# rs232-rs485-transceiver.net
KiCad netlist of a schematic drawn in Altium Designer
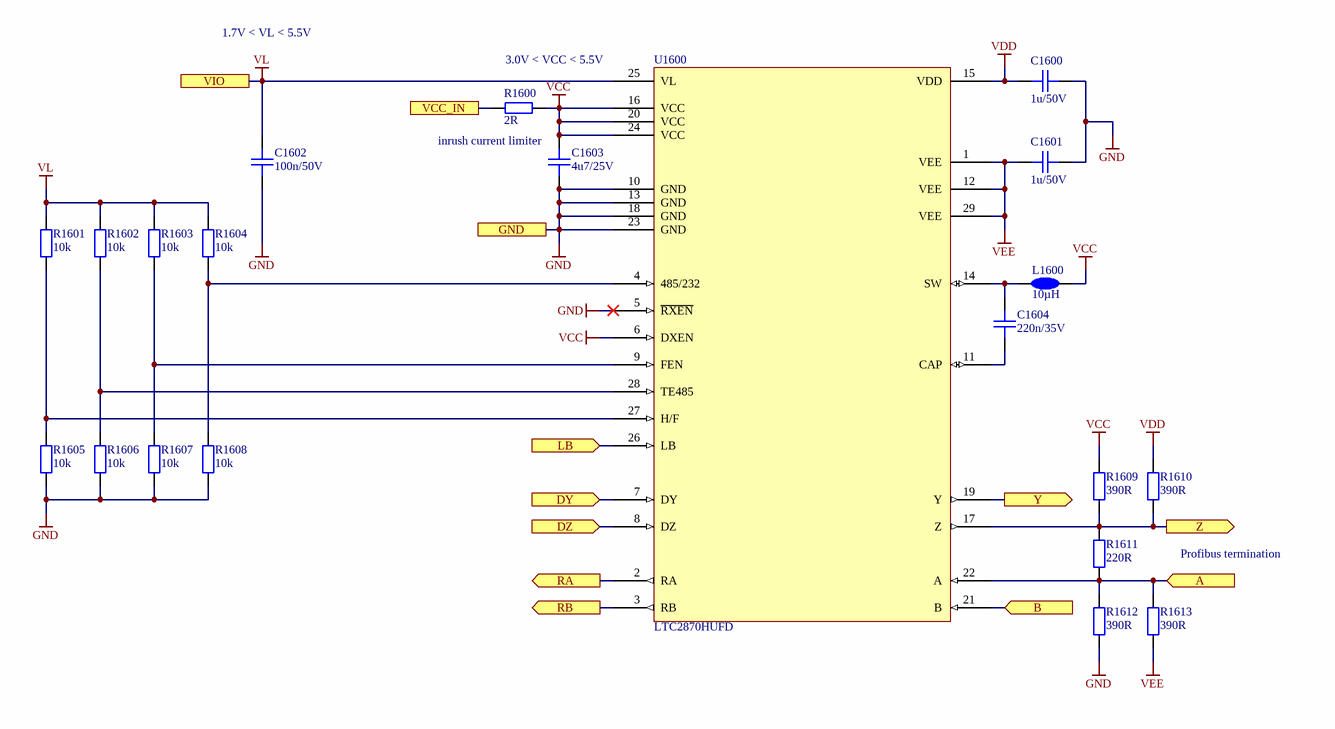
[diagram p0: rs232-rs485-transceiver.SchDoc]

(export (version "E")
  (design (tool "Eeschema 10.0.6"))
  (components
    (comp (ref "C1600")
      (value "1u/50V")
      (footprint "CAPC1608X08N")
      (description "MLCC")
      (fields (field (name "PART NUMBER") "gen_C_ceramic_1u_50V_X7R_0603") (field (name "TOLERANCE") "± 10%"))
      (libsource (lib "OE750") (part "C"))
    )
    (comp (ref "C1601")
      (value "1u/50V")
      (footprint "CAPC1608X08N")
      (description "MLCC")
      (fields (field (name "PART NUMBER") "gen_C_ceramic_1u_50V_X7R_0603") (field (name "TOLERANCE") "± 10%"))
      (libsource (lib "OE750") (part "C"))
    )
    (comp (ref "C1602")
      (value "100n/50V")
      (footprint "CAPC1005X06N")
      (description "MLCC")
      (fields (field (name "PART NUMBER") "gen_C_ceramic_100n_50V_X7R_0402"))
      (libsource (lib "OE750") (part "C"))
    )
    (comp (ref "C1603")
      (value "4u7/25V")
      (footprint "CAPC2012X14N")
      (description "MLCC")
      (fields (field (name "PART NUMBER") "gen_C_ceramic_4u7_25V_X7R_0805"))
      (libsource (lib "OE750") (part "C"))
    )
    (comp (ref "C1604")
      (value "220n/35V")
      (footprint "CAPC1005X06N")
      (description "MLCC")
      (fields (field (name "PART NUMBER") "gen_C_ceramic_220n_35V_X7R_0402"))
      (libsource (lib "OE750") (part "C"))
    )
    (comp (ref "L1600")
      (value "10µH")
      (footprint "INDC2012X14N")
      (description "Power Inductor")
      (fields (field (name "PART NUMBER") "LQM21DH100M70L") (field (name "MANUFACTURER") "Murata"))
      (libsource (lib "OE750") (part "L"))
    )
    (comp (ref "R1600")
      (value "2R")
      (footprint "RESC2012X05N")
      (description "SMD Resistor 2R 0805")
      (fields (field (name "PART NUMBER") "gen_R_2R_0805") (field (name "TOLERANCE") "1%"))
      (libsource (lib "OE750") (part "R"))
    )
    (comp (ref "R1601")
      (value "10k")
      (footprint "RESC1005X04N")
      (description "SMD Resistor 10k 0402")
      (fields (field (name "PART NUMBER") "gen_R_10k_0402") (field (name "TOLERANCE") "1%"))
      (libsource (lib "OE750") (part "R"))
    )
    (comp (ref "R1602")
      (value "10k")
      (footprint "RESC1005X04N")
      (description "SMD Resistor 10k 0402")
      (fields (field (name "PART NUMBER") "gen_R_10k_0402") (field (name "TOLERANCE") "1%"))
      (libsource (lib "OE750") (part "R"))
    )
    (comp (ref "R1603")
      (value "10k")
      (footprint "RESC1005X04N")
      (description "SMD Resistor 10k 0402")
      (fields (field (name "PART NUMBER") "gen_R_10k_0402") (field (name "TOLERANCE") "1%"))
      (libsource (lib "OE750") (part "R"))
    )
    (comp (ref "R1604")
      (value "10k")
      (footprint "RESC1005X04N")
      (description "SMD Resistor 10k 0402")
      (fields (field (name "PART NUMBER") "gen_R_10k_0402") (field (name "TOLERANCE") "1%"))
      (libsource (lib "OE750") (part "R"))
    )
    (comp (ref "R1605")
      (value "10k")
      (footprint "RESC1005X04N")
      (description "SMD Resistor 10k 0402")
      (fields (field (name "PART NUMBER") "gen_R_10k_0402") (field (name "TOLERANCE") "1%"))
      (libsource (lib "OE750") (part "R"))
    )
    (comp (ref "R1606")
      (value "10k")
      (footprint "RESC1005X04N")
      (description "SMD Resistor 10k 0402")
      (fields (field (name "PART NUMBER") "gen_R_10k_0402") (field (name "TOLERANCE") "1%"))
      (libsource (lib "OE750") (part "R"))
    )
    (comp (ref "R1607")
      (value "10k")
      (footprint "RESC1005X04N")
      (description "SMD Resistor 10k 0402")
      (fields (field (name "PART NUMBER") "gen_R_10k_0402") (field (name "TOLERANCE") "1%"))
      (libsource (lib "OE750") (part "R"))
    )
    (comp (ref "R1608")
      (value "10k")
      (footprint "RESC1005X04N")
      (description "SMD Resistor 10k 0402")
      (fields (field (name "PART NUMBER") "gen_R_10k_0402") (field (name "TOLERANCE") "1%"))
      (libsource (lib "OE750") (part "R"))
    )
    (comp (ref "R1609")
      (value "390R")
      (footprint "RESC1005X04N")
      (description "SMD Resistor 390R 0402")
      (fields (field (name "PART NUMBER") "gen_R_390R_0402") (field (name "TOLERANCE") "1%"))
      (libsource (lib "OE750") (part "R"))
    )
    (comp (ref "R1610")
      (value "390R")
      (footprint "RESC1005X04N")
      (description "SMD Resistor 390R 0402")
      (fields (field (name "PART NUMBER") "gen_R_390R_0402") (field (name "TOLERANCE") "1%"))
      (libsource (lib "OE750") (part "R"))
    )
    (comp (ref "R1611")
      (value "220R")
      (footprint "RESC1005X04N")
      (description "SMD Resistor 220R 0402")
      (fields (field (name "PART NUMBER") "gen_R_220R_0402") (field (name "TOLERANCE") "1%"))
      (libsource (lib "OE750") (part "R"))
    )
    (comp (ref "R1612")
      (value "390R")
      (footprint "RESC1005X04N")
      (description "SMD Resistor 390R 0402")
      (fields (field (name "PART NUMBER") "gen_R_390R_0402") (field (name "TOLERANCE") "1%"))
      (libsource (lib "OE750") (part "R"))
    )
    (comp (ref "R1613")
      (value "390R")
      (footprint "RESC1005X04N")
      (description "SMD Resistor 390R 0402")
      (fields (field (name "PART NUMBER") "gen_R_390R_0402") (field (name "TOLERANCE") "1%"))
      (libsource (lib "OE750") (part "R"))
    )
    (comp (ref "U1600")
      (value "LTC2870HUFD")
      (footprint "LTC2870-UFD")
      (description "RS-232-IC-Interface RS232/RS485 Multiprotocol Transceiver with Integrated Termination")
      (fields (field (name "MANUFACTURER") "Analog Devices"))
      (libsource (lib "OE750") (part "LTC2870"))
    )
  )
  (nets
    (net (code "1") (name "/A") (class "Default")
      (node (ref "R1611") (pin "1") (pinfunction "1_1") (pintype "passive"))
      (node (ref "R1612") (pin "2") (pinfunction "2_2") (pintype "passive"))
      (node (ref "R1613") (pin "2") (pinfunction "2_2") (pintype "passive"))
      (node (ref "U1600") (pin "22") (pinfunction "A_22") (pintype "input"))
    )
    (net (code "2") (name "/B") (class "Default")
      (node (ref "U1600") (pin "21") (pinfunction "B_21") (pintype "input"))
    )
    (net (code "3") (name "/DY") (class "Default")
      (node (ref "U1600") (pin "7") (pinfunction "DY_7") (pintype "input"))
    )
    (net (code "4") (name "/DZ") (class "Default")
      (node (ref "U1600") (pin "8") (pinfunction "DZ_8") (pintype "input"))
    )
    (net (code "5") (name "/LB") (class "Default")
      (node (ref "U1600") (pin "26") (pinfunction "LB_26") (pintype "input"))
    )
    (net (code "6") (name "/RA") (class "Default")
      (node (ref "U1600") (pin "2") (pinfunction "RA_2") (pintype "output"))
    )
    (net (code "7") (name "/RB") (class "Default")
      (node (ref "U1600") (pin "3") (pinfunction "RB_3") (pintype "output"))
    )
    (net (code "8") (name "/VCC_IN") (class "Default")
      (node (ref "R1600") (pin "1") (pinfunction "1_1") (pintype "passive"))
    )
    (net (code "9") (name "/Y") (class "Default")
      (node (ref "U1600") (pin "19") (pinfunction "Y_19") (pintype "output"))
    )
    (net (code "10") (name "/Z") (class "Default")
      (node (ref "R1609") (pin "1") (pinfunction "1_1") (pintype "passive"))
      (node (ref "R1610") (pin "1") (pinfunction "1_1") (pintype "passive"))
      (node (ref "R1611") (pin "2") (pinfunction "2_2") (pintype "passive"))
      (node (ref "U1600") (pin "17") (pinfunction "Z_17") (pintype "output"))
    )
    (net (code "11") (name "GND") (class "Default")
      (node (ref "C1600") (pin "2") (pinfunction "2_2") (pintype "passive"))
      (node (ref "C1601") (pin "2") (pinfunction "2_2") (pintype "passive"))
      (node (ref "C1602") (pin "1") (pinfunction "1_1") (pintype "passive"))
      (node (ref "C1603") (pin "1") (pinfunction "1_1") (pintype "passive"))
      (node (ref "R1605") (pin "1") (pinfunction "1_1") (pintype "passive"))
      (node (ref "R1606") (pin "1") (pinfunction "1_1") (pintype "passive"))
      (node (ref "R1607") (pin "1") (pinfunction "1_1") (pintype "passive"))
      (node (ref "R1608") (pin "1") (pinfunction "1_1") (pintype "passive"))
      (node (ref "R1612") (pin "1") (pinfunction "1_1") (pintype "passive"))
      (node (ref "U1600") (pin "10") (pinfunction "GND_10") (pintype "power_in"))
      (node (ref "U1600") (pin "13") (pinfunction "GND_13") (pintype "power_in"))
      (node (ref "U1600") (pin "18") (pinfunction "GND_18") (pintype "power_in"))
      (node (ref "U1600") (pin "23") (pinfunction "GND_23") (pintype "power_in"))
      (node (ref "U1600") (pin "5") (pinfunction "RXEN_5") (pintype "input"))
    )
    (net (code "12") (name "Net-(U1600-485{slash}232)") (class "Default")
      (node (ref "R1604") (pin "1") (pinfunction "1_1") (pintype "passive"))
      (node (ref "R1608") (pin "2") (pinfunction "2_2") (pintype "passive"))
      (node (ref "U1600") (pin "4") (pinfunction "485/232_4") (pintype "input"))
    )
    (net (code "13") (name "Net-(U1600-CAP)") (class "Default")
      (node (ref "C1604") (pin "1") (pinfunction "1_1") (pintype "passive"))
      (node (ref "U1600") (pin "11") (pinfunction "CAP_11") (pintype "bidirectional"))
    )
    (net (code "14") (name "Net-(U1600-FEN)") (class "Default")
      (node (ref "R1603") (pin "1") (pinfunction "1_1") (pintype "passive"))
      (node (ref "R1607") (pin "2") (pinfunction "2_2") (pintype "passive"))
      (node (ref "U1600") (pin "9") (pinfunction "FEN_9") (pintype "input"))
    )
    (net (code "15") (name "Net-(U1600-H{slash}F)") (class "Default")
      (node (ref "R1601") (pin "1") (pinfunction "1_1") (pintype "passive"))
      (node (ref "R1605") (pin "2") (pinfunction "2_2") (pintype "passive"))
      (node (ref "U1600") (pin "27") (pinfunction "H/F_27") (pintype "input"))
    )
    (net (code "16") (name "Net-(U1600-SW)") (class "Default")
      (node (ref "C1604") (pin "2") (pinfunction "2_2") (pintype "passive"))
      (node (ref "L1600") (pin "1") (pinfunction "1_1") (pintype "passive"))
      (node (ref "U1600") (pin "14") (pinfunction "SW_14") (pintype "bidirectional"))
    )
    (net (code "17") (name "Net-(U1600-TE485)") (class "Default")
      (node (ref "R1602") (pin "1") (pinfunction "1_1") (pintype "passive"))
      (node (ref "R1606") (pin "2") (pinfunction "2_2") (pintype "passive"))
      (node (ref "U1600") (pin "28") (pinfunction "TE485_28") (pintype "input"))
    )
    (net (code "18") (name "VCC") (class "Default")
      (node (ref "C1603") (pin "2") (pinfunction "2_2") (pintype "passive"))
      (node (ref "L1600") (pin "2") (pinfunction "2_2") (pintype "passive"))
      (node (ref "R1600") (pin "2") (pinfunction "2_2") (pintype "passive"))
      (node (ref "R1609") (pin "2") (pinfunction "2_2") (pintype "passive"))
      (node (ref "U1600") (pin "16") (pinfunction "VCC_16") (pintype "power_in"))
      (node (ref "U1600") (pin "20") (pinfunction "VCC_20") (pintype "power_in"))
      (node (ref "U1600") (pin "24") (pinfunction "VCC_24") (pintype "power_in"))
      (node (ref "U1600") (pin "6") (pinfunction "DXEN_6") (pintype "input"))
    )
    (net (code "19") (name "VDD") (class "Default")
      (node (ref "C1600") (pin "1") (pinfunction "1_1") (pintype "passive"))
      (node (ref "R1610") (pin "2") (pinfunction "2_2") (pintype "passive"))
      (node (ref "U1600") (pin "15") (pinfunction "VDD_15") (pintype "power_in"))
    )
    (net (code "20") (name "VEE") (class "Default")
      (node (ref "C1601") (pin "1") (pinfunction "1_1") (pintype "passive"))
      (node (ref "R1613") (pin "1") (pinfunction "1_1") (pintype "passive"))
      (node (ref "U1600") (pin "1") (pinfunction "VEE_1") (pintype "power_in"))
      (node (ref "U1600") (pin "12") (pinfunction "VEE_12") (pintype "power_in"))
      (node (ref "U1600") (pin "29") (pinfunction "VEE_29") (pintype "power_in"))
    )
    (net (code "21") (name "VL") (class "Default")
      (node (ref "C1602") (pin "2") (pinfunction "2_2") (pintype "passive"))
      (node (ref "R1601") (pin "2") (pinfunction "2_2") (pintype "passive"))
      (node (ref "R1602") (pin "2") (pinfunction "2_2") (pintype "passive"))
      (node (ref "R1603") (pin "2") (pinfunction "2_2") (pintype "passive"))
      (node (ref "R1604") (pin "2") (pinfunction "2_2") (pintype "passive"))
      (node (ref "U1600") (pin "25") (pinfunction "VL_25") (pintype "power_in"))
    )
  )
)
